# Header.net
KiCad netlist of a schematic drawn in EAGLE
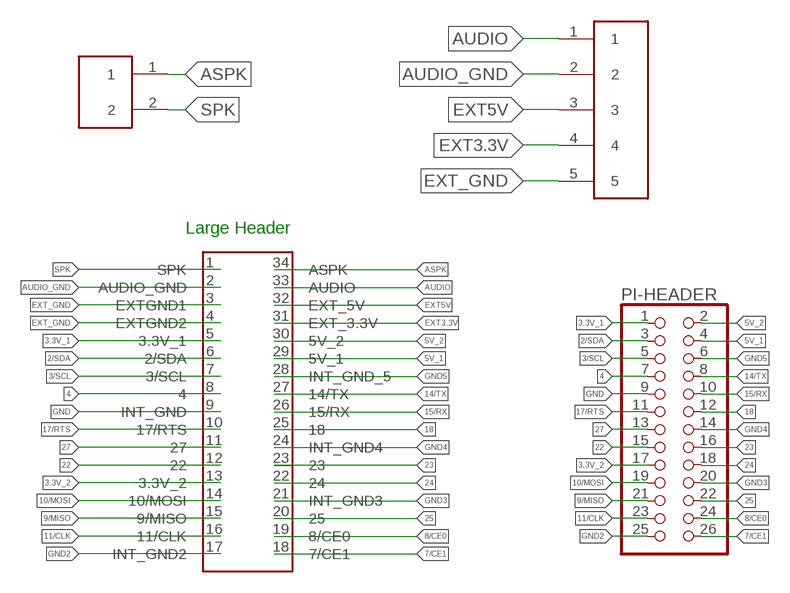
[diagram p0: schematic, sheet 1]

(export (version "E")
  (design (tool "Eeschema 10.0.6"))
  (components
    (comp (ref "PI-HEADER")
      (value "PINHD-2X13")
      (footprint "eagle-import:2X13")
      (libsource (lib "eagle-import") (part "PINHD-2X13"))
    )
    (comp (ref "U$1")
      (value "2X17HEADER")
      (footprint "eagle-import:2X32HEADER")
      (libsource (lib "eagle-import") (part "2X17HEADER"))
    )
    (comp (ref "U$2")
      (value "DF3_1X5")
      (footprint "eagle-import:DF3_1X5")
      (libsource (lib "eagle-import") (part "DF3_1X5"))
    )
    (comp (ref "U$4")
      (value "DF3_1X2")
      (footprint "eagle-import:DF3_1X2")
      (libsource (lib "eagle-import") (part "DF3_1X2"))
    )
  )
  (nets
    (net (code "1") (name "2{slash}SDA") (class "Default")
      (node (ref "PI-HEADER") (pin "3") (pinfunction "3_3") (pintype "passive"))
      (node (ref "U$1") (pin "6") (pinfunction "2/SDA_6") (pintype "output"))
    )
    (net (code "2") (name "3.3V_1") (class "Default")
      (node (ref "PI-HEADER") (pin "1") (pinfunction "1_1") (pintype "passive"))
      (node (ref "U$1") (pin "5") (pinfunction "3.3V_1_5") (pintype "output"))
    )
    (net (code "3") (name "3.3V_2") (class "Default")
      (node (ref "PI-HEADER") (pin "17") (pinfunction "17_17") (pintype "passive"))
      (node (ref "U$1") (pin "13") (pinfunction "3.3V_2_13") (pintype "output"))
    )
    (net (code "4") (name "3{slash}SCL") (class "Default")
      (node (ref "PI-HEADER") (pin "5") (pinfunction "5_5") (pintype "passive"))
      (node (ref "U$1") (pin "7") (pinfunction "3/SCL_7") (pintype "output"))
    )
    (net (code "5") (name "4") (class "Default")
      (node (ref "PI-HEADER") (pin "7") (pinfunction "7_7") (pintype "passive"))
      (node (ref "U$1") (pin "8") (pinfunction "4_8") (pintype "output"))
    )
    (net (code "6") (name "5V_1") (class "Default")
      (node (ref "PI-HEADER") (pin "4") (pinfunction "4_4") (pintype "passive"))
      (node (ref "U$1") (pin "29") (pinfunction "5V_1_29") (pintype "output"))
    )
    (net (code "7") (name "5V_2") (class "Default")
      (node (ref "PI-HEADER") (pin "2") (pinfunction "2_2") (pintype "passive"))
      (node (ref "U$1") (pin "30") (pinfunction "5V_2_30") (pintype "output"))
    )
    (net (code "8") (name "7{slash}CE1") (class "Default")
      (node (ref "PI-HEADER") (pin "26") (pinfunction "26_26") (pintype "passive"))
      (node (ref "U$1") (pin "18") (pinfunction "7/CE1_18") (pintype "output"))
    )
    (net (code "9") (name "8{slash}CE0") (class "Default")
      (node (ref "PI-HEADER") (pin "24") (pinfunction "24_24") (pintype "passive"))
      (node (ref "U$1") (pin "19") (pinfunction "8/CE0_19") (pintype "output"))
    )
    (net (code "10") (name "9{slash}MISO") (class "Default")
      (node (ref "PI-HEADER") (pin "21") (pinfunction "21_21") (pintype "passive"))
      (node (ref "U$1") (pin "15") (pinfunction "9/MISO_15") (pintype "output"))
    )
    (net (code "11") (name "10{slash}MOSI") (class "Default")
      (node (ref "PI-HEADER") (pin "19") (pinfunction "19_19") (pintype "passive"))
      (node (ref "U$1") (pin "14") (pinfunction "10/MOSI_14") (pintype "output"))
    )
    (net (code "12") (name "11{slash}CLK") (class "Default")
      (node (ref "PI-HEADER") (pin "23") (pinfunction "23_23") (pintype "passive"))
      (node (ref "U$1") (pin "16") (pinfunction "11/CLK_16") (pintype "output"))
    )
    (net (code "13") (name "14{slash}TX") (class "Default")
      (node (ref "PI-HEADER") (pin "8") (pinfunction "8_8") (pintype "passive"))
      (node (ref "U$1") (pin "27") (pinfunction "14/TX_27") (pintype "output"))
    )
    (net (code "14") (name "15{slash}RX") (class "Default")
      (node (ref "PI-HEADER") (pin "10") (pinfunction "10_10") (pintype "passive"))
      (node (ref "U$1") (pin "26") (pinfunction "15/RX_26") (pintype "output"))
    )
    (net (code "15") (name "17{slash}RTS") (class "Default")
      (node (ref "PI-HEADER") (pin "11") (pinfunction "11_11") (pintype "passive"))
      (node (ref "U$1") (pin "10") (pinfunction "17/RTS_10") (pintype "output"))
    )
    (net (code "16") (name "18") (class "Default")
      (node (ref "PI-HEADER") (pin "12") (pinfunction "12_12") (pintype "passive"))
      (node (ref "U$1") (pin "25") (pinfunction "18_25") (pintype "output"))
    )
    (net (code "17") (name "22") (class "Default")
      (node (ref "PI-HEADER") (pin "15") (pinfunction "15_15") (pintype "passive"))
      (node (ref "U$1") (pin "12") (pinfunction "22_12") (pintype "output"))
    )
    (net (code "18") (name "23") (class "Default")
      (node (ref "PI-HEADER") (pin "16") (pinfunction "16_16") (pintype "passive"))
      (node (ref "U$1") (pin "23") (pinfunction "23_23") (pintype "output"))
    )
    (net (code "19") (name "24") (class "Default")
      (node (ref "PI-HEADER") (pin "18") (pinfunction "18_18") (pintype "passive"))
      (node (ref "U$1") (pin "22") (pinfunction "24_22") (pintype "output"))
    )
    (net (code "20") (name "25") (class "Default")
      (node (ref "PI-HEADER") (pin "22") (pinfunction "22_22") (pintype "passive"))
      (node (ref "U$1") (pin "20") (pinfunction "25_20") (pintype "output"))
    )
    (net (code "21") (name "27") (class "Default")
      (node (ref "PI-HEADER") (pin "13") (pinfunction "13_13") (pintype "passive"))
      (node (ref "U$1") (pin "11") (pinfunction "27_11") (pintype "output"))
    )
    (net (code "22") (name "ASPK") (class "Default")
      (node (ref "U$1") (pin "34") (pinfunction "ASPK_34") (pintype "output"))
      (node (ref "U$4") (pin "1") (pinfunction "1_1") (pintype "bidirectional"))
    )
    (net (code "23") (name "AUDIO") (class "Default")
      (node (ref "U$1") (pin "33") (pinfunction "AUDIO_33") (pintype "output"))
      (node (ref "U$2") (pin "1") (pinfunction "1_1") (pintype "bidirectional"))
    )
    (net (code "24") (name "AUDIO_GND") (class "Default")
      (node (ref "U$1") (pin "2") (pinfunction "AUDIO_GND_2") (pintype "output"))
      (node (ref "U$2") (pin "2") (pinfunction "2_2") (pintype "bidirectional"))
    )
    (net (code "25") (name "EXT3.3V") (class "Default")
      (node (ref "U$1") (pin "31") (pinfunction "EXT_3.3V_31") (pintype "output"))
      (node (ref "U$2") (pin "4") (pinfunction "4_4") (pintype "bidirectional"))
    )
    (net (code "26") (name "EXT5V") (class "Default")
      (node (ref "U$1") (pin "32") (pinfunction "EXT_5V_32") (pintype "output"))
      (node (ref "U$2") (pin "3") (pinfunction "3_3") (pintype "bidirectional"))
    )
    (net (code "27") (name "EXT_GND") (class "Default")
      (node (ref "U$1") (pin "3") (pinfunction "EXTGND1_3") (pintype "output"))
      (node (ref "U$1") (pin "4") (pinfunction "EXTGND2_4") (pintype "output"))
      (node (ref "U$2") (pin "5") (pinfunction "5_5") (pintype "bidirectional"))
    )
    (net (code "28") (name "GND") (class "Default")
      (node (ref "PI-HEADER") (pin "9") (pinfunction "9_9") (pintype "passive"))
      (node (ref "U$1") (pin "9") (pinfunction "INT_GND_9") (pintype "output"))
    )
    (net (code "29") (name "GND2") (class "Default")
      (node (ref "PI-HEADER") (pin "25") (pinfunction "25_25") (pintype "passive"))
      (node (ref "U$1") (pin "17") (pinfunction "INT_GND2_17") (pintype "output"))
    )
    (net (code "30") (name "GND3") (class "Default")
      (node (ref "PI-HEADER") (pin "20") (pinfunction "20_20") (pintype "passive"))
      (node (ref "U$1") (pin "21") (pinfunction "INT_GND3_21") (pintype "output"))
    )
    (net (code "31") (name "GND4") (class "Default")
      (node (ref "PI-HEADER") (pin "14") (pinfunction "14_14") (pintype "passive"))
      (node (ref "U$1") (pin "24") (pinfunction "INT_GND4_24") (pintype "output"))
    )
    (net (code "32") (name "GND5") (class "Default")
      (node (ref "PI-HEADER") (pin "6") (pinfunction "6_6") (pintype "passive"))
      (node (ref "U$1") (pin "28") (pinfunction "INT_GND_5_28") (pintype "output"))
    )
    (net (code "33") (name "SPK") (class "Default")
      (node (ref "U$1") (pin "1") (pinfunction "SPK_1") (pintype "output"))
      (node (ref "U$4") (pin "2") (pinfunction "2_2") (pintype "bidirectional"))
    )
  )
)
